# USB_C_programmer_1.net
KiCad netlist of a schematic drawn in Altium Designer
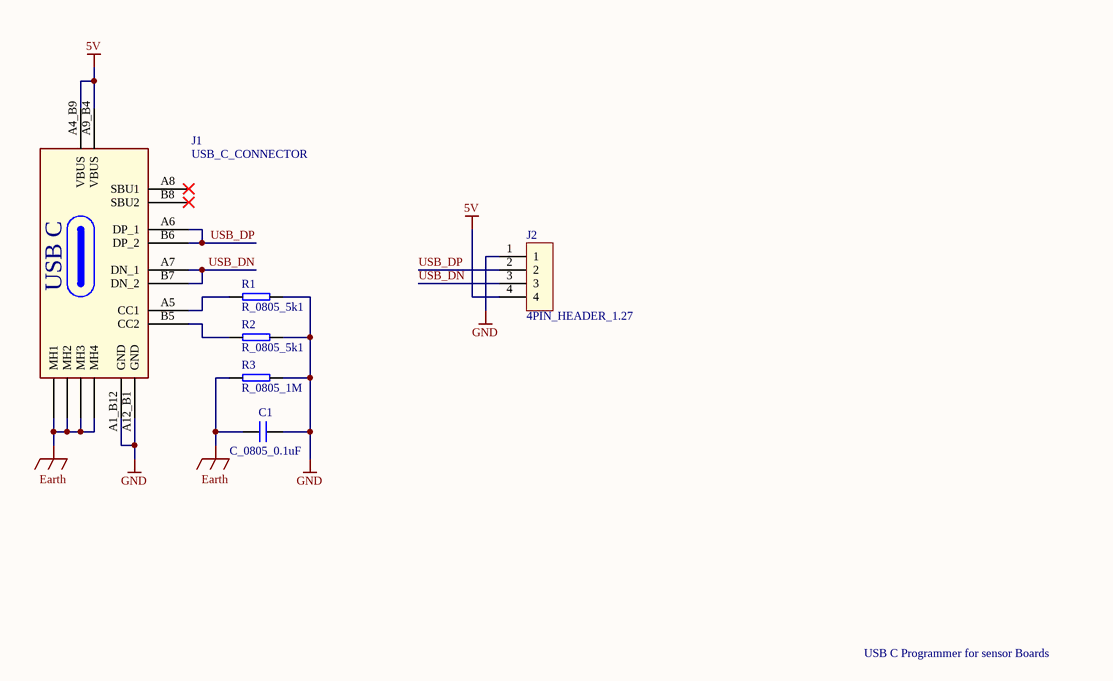
[diagram p0: USB_C_programmer_1.SchDoc]

(export (version "E")
  (design (tool "Eeschema 10.0.6"))
  (components
    (comp (ref "C1")
      (value "C_0805_0.1uF")
      (footprint "CAP_0805")
      (fields (field (name "JLC PART NUMBER") "C28233"))
      (libsource (lib "Petar B") (part "0.1uF 0805"))
    )
    (comp (ref "J1")
      (value "USB_C_CONNECTOR")
      (footprint "USB_C_CONNECTOR-Footprint-1")
      (description "USB2.0, Type C, Top Mount, Ch 1.68MM, Dual Row SMT / Tap/rl")
      (fields (field (name "JLC PART NUMBER") "C2831450"))
      (libsource (lib "Petar B") (part "conn_usb_c"))
    )
    (comp (ref "J2")
      (value "4PIN_HEADER_1.27")
      (footprint "4PIN_HEADER_1.27-Footprint-1")
      (libsource (lib "Petar B") (part "4PIN_HEADER_1.27-Symbol-1"))
    )
    (comp (ref "R1")
      (value "R_0805_5k1")
      (footprint "0805_RES")
      (fields (field (name "JLC PART NUMBER") "C27834"))
      (libsource (lib "Petar B") (part "4.7k0805"))
    )
    (comp (ref "R2")
      (value "R_0805_5k1")
      (footprint "0805_RES")
      (fields (field (name "JLC PART NUMBER") "C27834"))
      (libsource (lib "Petar B") (part "4.7k0805"))
    )
    (comp (ref "R3")
      (value "R_0805_1M")
      (footprint "0805_RES")
      (fields (field (name "JLC PART NUMBER") "C131391"))
      (libsource (lib "Petar B") (part "R_symbol"))
    )
  )
  (nets
    (net (code "1") (name "/USB_DN") (class "Default")
      (node (ref "J1") (pin "A7") (pinfunction "DN_1_A7") (pintype "passive"))
      (node (ref "J1") (pin "B7") (pinfunction "DN_2_B7") (pintype "passive"))
      (node (ref "J2") (pin "3") (pinfunction "3_3") (pintype "passive"))
    )
    (net (code "2") (name "/USB_DP") (class "Default")
      (node (ref "J1") (pin "A6") (pinfunction "DP_1_A6") (pintype "passive"))
      (node (ref "J1") (pin "B6") (pinfunction "DP_2_B6") (pintype "passive"))
      (node (ref "J2") (pin "2") (pinfunction "2_2") (pintype "passive"))
    )
    (net (code "3") (name "5V") (class "Default")
      (node (ref "J1") (pin "A4_B9") (pinfunction "VBUS_A4_B9") (pintype "passive"))
      (node (ref "J1") (pin "A9_B4") (pinfunction "VBUS_A9_B4") (pintype "passive"))
      (node (ref "J2") (pin "4") (pinfunction "4_4") (pintype "passive"))
    )
    (net (code "4") (name "Earth") (class "Default")
      (node (ref "C1") (pin "1") (pinfunction "1_1") (pintype "passive"))
      (node (ref "J1") (pin "MH1") (pinfunction "MH1_MH1") (pintype "passive"))
      (node (ref "J1") (pin "MH2") (pinfunction "MH2_MH2") (pintype "passive"))
      (node (ref "J1") (pin "MH3") (pinfunction "MH3_MH3") (pintype "passive"))
      (node (ref "J1") (pin "MH4") (pinfunction "MH4_MH4") (pintype "passive"))
      (node (ref "R3") (pin "2") (pinfunction "2_2") (pintype "passive"))
    )
    (net (code "5") (name "GND") (class "Default")
      (node (ref "C1") (pin "2") (pinfunction "2_2") (pintype "passive"))
      (node (ref "J1") (pin "A12_B1") (pinfunction "GND_A12_B1") (pintype "passive"))
      (node (ref "J1") (pin "A1_B12") (pinfunction "GND_A1_B12") (pintype "passive"))
      (node (ref "J2") (pin "1") (pinfunction "1_1") (pintype "passive"))
      (node (ref "R1") (pin "1") (pinfunction "1_1") (pintype "passive"))
      (node (ref "R2") (pin "1") (pinfunction "1_1") (pintype "passive"))
      (node (ref "R3") (pin "1") (pinfunction "1_1") (pintype "passive"))
    )
    (net (code "6") (name "Net-(J1-CC1)") (class "Default")
      (node (ref "J1") (pin "A5") (pinfunction "CC1_A5") (pintype "passive"))
      (node (ref "R1") (pin "2") (pinfunction "2_2") (pintype "passive"))
    )
    (net (code "7") (name "Net-(J1-CC2)") (class "Default")
      (node (ref "J1") (pin "B5") (pinfunction "CC2_B5") (pintype "passive"))
      (node (ref "R2") (pin "2") (pinfunction "2_2") (pintype "passive"))
    )
    (net (code "8") (name "unconnected-(J1-SBU1-PadA8)") (class "Default")
      (node (ref "J1") (pin "A8") (pinfunction "SBU1_A8") (pintype "passive+no_connect"))
    )
    (net (code "9") (name "unconnected-(J1-SBU2-PadB8)") (class "Default")
      (node (ref "J1") (pin "B8") (pinfunction "SBU2_B8") (pintype "passive+no_connect"))
    )
  )
)
